# SENSOR.net
KiCad netlist of a schematic drawn in Altium Designer
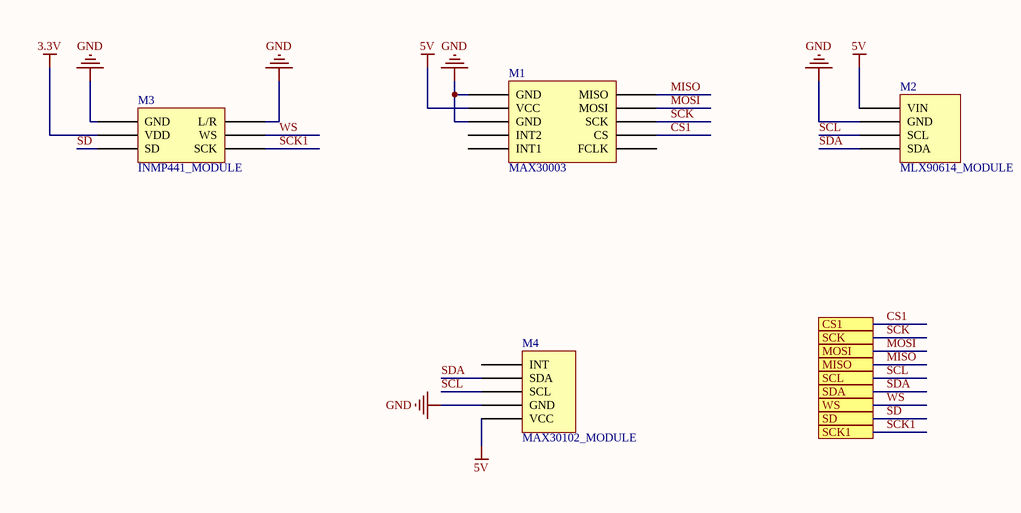
[diagram p0: SENSOR.SchDoc]

(export (version "E")
  (design (tool "Eeschema 10.0.6"))
  (components
    (comp (ref "M1")
      (value "MAX30003")
      (footprint "MAX30003")
      (libsource (lib "KHOEMACH_LIB") (part "MAX30003"))
    )
    (comp (ref "M2")
      (value "MLX90614_MODULE")
      (footprint "MLX90614_MODULE")
      (libsource (lib "KHOEMACH_LIB") (part "MLX90614_MODULE"))
    )
    (comp (ref "M3")
      (value "INMP441_MODULE")
      (footprint "INMP441_MODULE")
      (libsource (lib "KHOEMACH_LIB") (part "INMP441_MODULE"))
    )
    (comp (ref "M4")
      (value "MAX30102_MODULE")
      (footprint "MAX30102_module")
      (libsource (lib "KHOEMACH_LIB") (part "MAX30102_MODULE"))
    )
  )
  (nets
    (net (code "1") (name "/CS1") (class "Default")
      (node (ref "M1") (pin "CS") (pinfunction "CS_CS") (pintype "passive"))
    )
    (net (code "2") (name "/MISO") (class "Default")
      (node (ref "M1") (pin "MISO") (pinfunction "MISO_MISO") (pintype "passive"))
    )
    (net (code "3") (name "/MOSI") (class "Default")
      (node (ref "M1") (pin "MOSI") (pinfunction "MOSI_MOSI") (pintype "passive"))
    )
    (net (code "4") (name "/SCK") (class "Default")
      (node (ref "M1") (pin "SCK") (pinfunction "SCK_SCK") (pintype "passive"))
    )
    (net (code "5") (name "/SCK1") (class "Default")
      (node (ref "M3") (pin "6") (pinfunction "SCK_6") (pintype "passive"))
    )
    (net (code "6") (name "/SCL") (class "Default")
      (node (ref "M2") (pin "3") (pinfunction "SCL_3") (pintype "passive"))
      (node (ref "M4") (pin "3") (pinfunction "SCL_3") (pintype "passive"))
    )
    (net (code "7") (name "/SD") (class "Default")
      (node (ref "M3") (pin "3") (pinfunction "SD_3") (pintype "passive"))
    )
    (net (code "8") (name "/SDA") (class "Default")
      (node (ref "M2") (pin "4") (pinfunction "SDA_4") (pintype "passive"))
      (node (ref "M4") (pin "2") (pinfunction "SDA_2") (pintype "passive"))
    )
    (net (code "9") (name "/WS") (class "Default")
      (node (ref "M3") (pin "5") (pinfunction "WS_5") (pintype "passive"))
    )
    (net (code "10") (name "3.3V") (class "Default")
      (node (ref "M3") (pin "2") (pinfunction "VDD_2") (pintype "passive"))
    )
    (net (code "11") (name "5V") (class "Default")
      (node (ref "M1") (pin "VCC") (pinfunction "VCC_VCC") (pintype "passive"))
      (node (ref "M2") (pin "1") (pinfunction "VIN_1") (pintype "passive"))
      (node (ref "M4") (pin "5") (pinfunction "VCC_5") (pintype "passive"))
    )
    (net (code "12") (name "GND") (class "Default")
      (node (ref "M1") (pin "GND") (pinfunction "GND_GND") (pintype "passive"))
      (node (ref "M2") (pin "2") (pinfunction "GND_2") (pintype "passive"))
      (node (ref "M3") (pin "1") (pinfunction "GND_1") (pintype "passive"))
      (node (ref "M3") (pin "4") (pinfunction "L/R_4") (pintype "passive"))
      (node (ref "M4") (pin "4") (pinfunction "GND_4") (pintype "passive"))
    )
    (net (code "13") (name "unconnected-(M1-PadFCLK)") (class "Default")
      (node (ref "M1") (pin "FCLK") (pinfunction "FCLK_FCLK") (pintype "passive"))
    )
    (net (code "14") (name "unconnected-(M1-PadINT1)") (class "Default")
      (node (ref "M1") (pin "INT1") (pinfunction "INT1_INT1") (pintype "passive"))
    )
    (net (code "15") (name "unconnected-(M1-PadINT2)") (class "Default")
      (node (ref "M1") (pin "INT2") (pinfunction "INT2_INT2") (pintype "passive"))
    )
    (net (code "16") (name "unconnected-(M4-INT-Pad1)") (class "Default")
      (node (ref "M4") (pin "1") (pinfunction "INT_1") (pintype "passive"))
    )
  )
)
